# flatsat-breakout-main.net
KiCad netlist of a schematic drawn in EAGLE
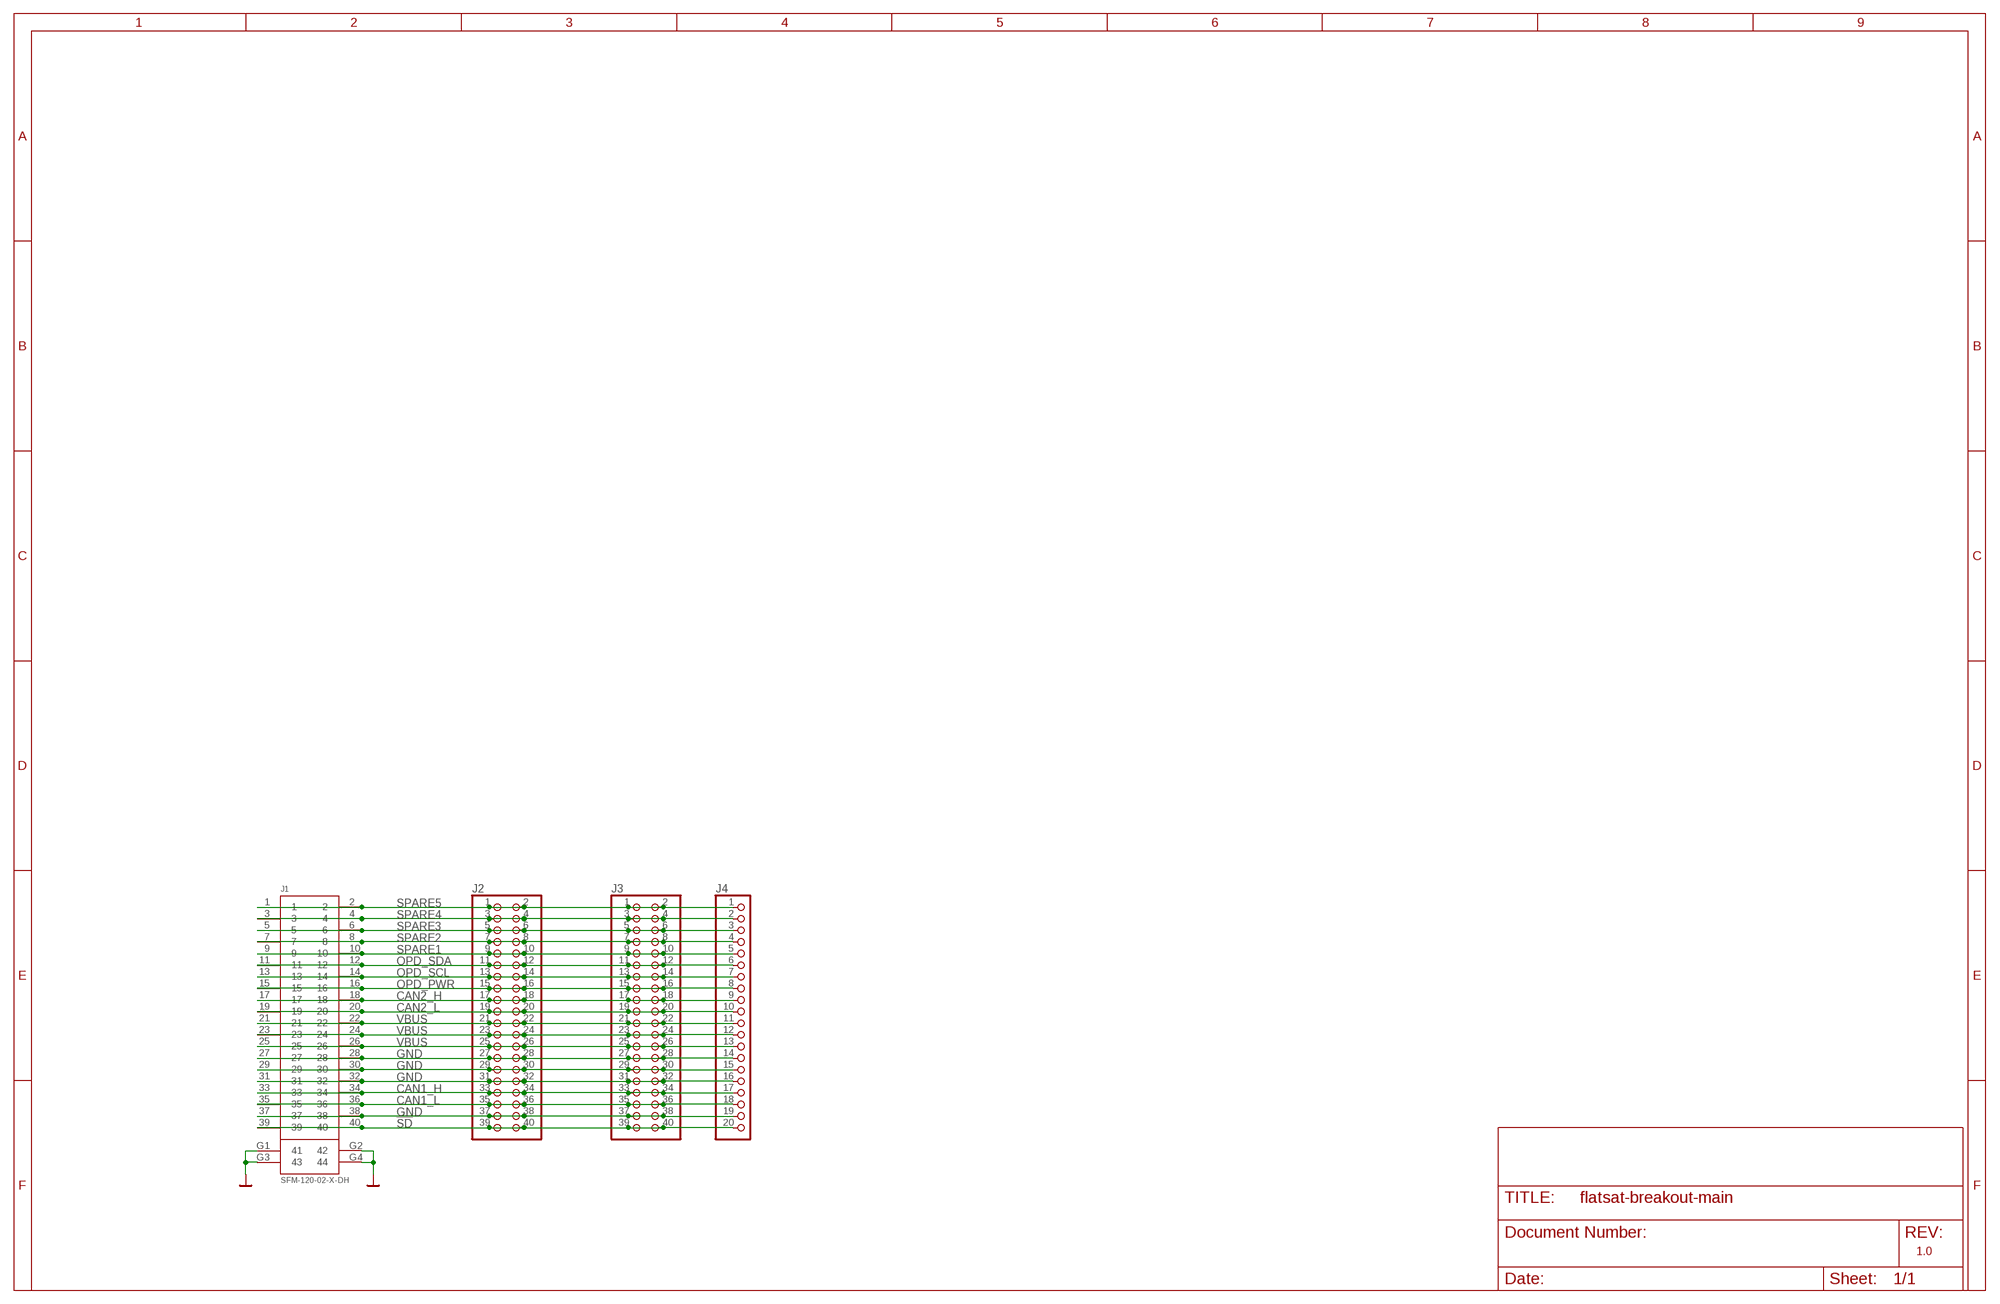
[diagram p0: schematic, sheet 1]

(export (version "E")
  (design (tool "Eeschema 10.0.6"))
  (components
    (comp (ref "J1")
      (value "SFM-120-02-X-DH")
      (footprint "eagle-import:SFM-120-02-X-DH")
      (libsource (lib "eagle-import") (part "SFM-120-02-X-DH"))
    )
    (comp (ref "J2")
      (value "PINHD-2X20")
      (footprint "eagle-import:2X20")
      (libsource (lib "eagle-import") (part "PINHD-2X20"))
    )
    (comp (ref "J3")
      (value "PINHD-2X20")
      (footprint "eagle-import:2X20")
      (libsource (lib "eagle-import") (part "PINHD-2X20"))
    )
    (comp (ref "J4")
      (value "PINHD-1X20")
      (footprint "eagle-import:1X20")
      (libsource (lib "eagle-import") (part "PINHD-1X20"))
    )
  )
  (nets
    (net (code "1") (name "/CAN1_H") (class "Default")
      (node (ref "J1") (pin "33") (pinfunction "33_33") (pintype "bidirectional"))
      (node (ref "J1") (pin "34") (pinfunction "34_34") (pintype "bidirectional"))
      (node (ref "J2") (pin "33") (pinfunction "33_33") (pintype "passive"))
      (node (ref "J2") (pin "34") (pinfunction "34_34") (pintype "passive"))
      (node (ref "J3") (pin "33") (pinfunction "33_33") (pintype "passive"))
      (node (ref "J3") (pin "34") (pinfunction "34_34") (pintype "passive"))
      (node (ref "J4") (pin "17") (pinfunction "17_17") (pintype "passive"))
    )
    (net (code "2") (name "/CAN1_L") (class "Default")
      (node (ref "J1") (pin "35") (pinfunction "35_35") (pintype "bidirectional"))
      (node (ref "J1") (pin "36") (pinfunction "36_36") (pintype "bidirectional"))
      (node (ref "J2") (pin "35") (pinfunction "35_35") (pintype "passive"))
      (node (ref "J2") (pin "36") (pinfunction "36_36") (pintype "passive"))
      (node (ref "J3") (pin "35") (pinfunction "35_35") (pintype "passive"))
      (node (ref "J3") (pin "36") (pinfunction "36_36") (pintype "passive"))
      (node (ref "J4") (pin "18") (pinfunction "18_18") (pintype "passive"))
    )
    (net (code "3") (name "/CAN2_H") (class "Default")
      (node (ref "J1") (pin "17") (pinfunction "17_17") (pintype "bidirectional"))
      (node (ref "J1") (pin "18") (pinfunction "18_18") (pintype "bidirectional"))
      (node (ref "J2") (pin "17") (pinfunction "17_17") (pintype "passive"))
      (node (ref "J2") (pin "18") (pinfunction "18_18") (pintype "passive"))
      (node (ref "J3") (pin "17") (pinfunction "17_17") (pintype "passive"))
      (node (ref "J3") (pin "18") (pinfunction "18_18") (pintype "passive"))
      (node (ref "J4") (pin "9") (pinfunction "9_9") (pintype "passive"))
    )
    (net (code "4") (name "/CAN2_L") (class "Default")
      (node (ref "J1") (pin "19") (pinfunction "19_19") (pintype "bidirectional"))
      (node (ref "J1") (pin "20") (pinfunction "20_20") (pintype "bidirectional"))
      (node (ref "J2") (pin "19") (pinfunction "19_19") (pintype "passive"))
      (node (ref "J2") (pin "20") (pinfunction "20_20") (pintype "passive"))
      (node (ref "J3") (pin "19") (pinfunction "19_19") (pintype "passive"))
      (node (ref "J3") (pin "20") (pinfunction "20_20") (pintype "passive"))
      (node (ref "J4") (pin "10") (pinfunction "10_10") (pintype "passive"))
    )
    (net (code "5") (name "/OPD_PWR") (class "Default")
      (node (ref "J1") (pin "15") (pinfunction "15_15") (pintype "bidirectional"))
      (node (ref "J1") (pin "16") (pinfunction "16_16") (pintype "bidirectional"))
      (node (ref "J2") (pin "15") (pinfunction "15_15") (pintype "passive"))
      (node (ref "J2") (pin "16") (pinfunction "16_16") (pintype "passive"))
      (node (ref "J3") (pin "15") (pinfunction "15_15") (pintype "passive"))
      (node (ref "J3") (pin "16") (pinfunction "16_16") (pintype "passive"))
      (node (ref "J4") (pin "8") (pinfunction "8_8") (pintype "passive"))
    )
    (net (code "6") (name "/OPD_SCL") (class "Default")
      (node (ref "J1") (pin "13") (pinfunction "13_13") (pintype "bidirectional"))
      (node (ref "J1") (pin "14") (pinfunction "14_14") (pintype "bidirectional"))
      (node (ref "J2") (pin "13") (pinfunction "13_13") (pintype "passive"))
      (node (ref "J2") (pin "14") (pinfunction "14_14") (pintype "passive"))
      (node (ref "J3") (pin "13") (pinfunction "13_13") (pintype "passive"))
      (node (ref "J3") (pin "14") (pinfunction "14_14") (pintype "passive"))
      (node (ref "J4") (pin "7") (pinfunction "7_7") (pintype "passive"))
    )
    (net (code "7") (name "/OPD_SDA") (class "Default")
      (node (ref "J1") (pin "11") (pinfunction "11_11") (pintype "bidirectional"))
      (node (ref "J1") (pin "12") (pinfunction "12_12") (pintype "bidirectional"))
      (node (ref "J2") (pin "11") (pinfunction "11_11") (pintype "passive"))
      (node (ref "J2") (pin "12") (pinfunction "12_12") (pintype "passive"))
      (node (ref "J3") (pin "11") (pinfunction "11_11") (pintype "passive"))
      (node (ref "J3") (pin "12") (pinfunction "12_12") (pintype "passive"))
      (node (ref "J4") (pin "6") (pinfunction "6_6") (pintype "passive"))
    )
    (net (code "8") (name "/SPARE1") (class "Default")
      (node (ref "J1") (pin "10") (pinfunction "10_10") (pintype "bidirectional"))
      (node (ref "J1") (pin "9") (pinfunction "9_9") (pintype "bidirectional"))
      (node (ref "J2") (pin "10") (pinfunction "10_10") (pintype "passive"))
      (node (ref "J2") (pin "9") (pinfunction "9_9") (pintype "passive"))
      (node (ref "J3") (pin "10") (pinfunction "10_10") (pintype "passive"))
      (node (ref "J3") (pin "9") (pinfunction "9_9") (pintype "passive"))
      (node (ref "J4") (pin "5") (pinfunction "5_5") (pintype "passive"))
    )
    (net (code "9") (name "/SPARE2") (class "Default")
      (node (ref "J1") (pin "7") (pinfunction "7_7") (pintype "bidirectional"))
      (node (ref "J1") (pin "8") (pinfunction "8_8") (pintype "bidirectional"))
      (node (ref "J2") (pin "7") (pinfunction "7_7") (pintype "passive"))
      (node (ref "J2") (pin "8") (pinfunction "8_8") (pintype "passive"))
      (node (ref "J3") (pin "7") (pinfunction "7_7") (pintype "passive"))
      (node (ref "J3") (pin "8") (pinfunction "8_8") (pintype "passive"))
      (node (ref "J4") (pin "4") (pinfunction "4_4") (pintype "passive"))
    )
    (net (code "10") (name "/SPARE3") (class "Default")
      (node (ref "J1") (pin "5") (pinfunction "5_5") (pintype "bidirectional"))
      (node (ref "J1") (pin "6") (pinfunction "6_6") (pintype "bidirectional"))
      (node (ref "J2") (pin "5") (pinfunction "5_5") (pintype "passive"))
      (node (ref "J2") (pin "6") (pinfunction "6_6") (pintype "passive"))
      (node (ref "J3") (pin "5") (pinfunction "5_5") (pintype "passive"))
      (node (ref "J3") (pin "6") (pinfunction "6_6") (pintype "passive"))
      (node (ref "J4") (pin "3") (pinfunction "3_3") (pintype "passive"))
    )
    (net (code "11") (name "/SPARE4") (class "Default")
      (node (ref "J1") (pin "3") (pinfunction "3_3") (pintype "bidirectional"))
      (node (ref "J1") (pin "4") (pinfunction "4_4") (pintype "bidirectional"))
      (node (ref "J2") (pin "3") (pinfunction "3_3") (pintype "passive"))
      (node (ref "J2") (pin "4") (pinfunction "4_4") (pintype "passive"))
      (node (ref "J3") (pin "3") (pinfunction "3_3") (pintype "passive"))
      (node (ref "J3") (pin "4") (pinfunction "4_4") (pintype "passive"))
      (node (ref "J4") (pin "2") (pinfunction "2_2") (pintype "passive"))
    )
    (net (code "12") (name "/SPARE5") (class "Default")
      (node (ref "J1") (pin "1") (pinfunction "1_1") (pintype "bidirectional"))
      (node (ref "J1") (pin "2") (pinfunction "2_2") (pintype "bidirectional"))
      (node (ref "J2") (pin "1") (pinfunction "1_1") (pintype "passive"))
      (node (ref "J2") (pin "2") (pinfunction "2_2") (pintype "passive"))
      (node (ref "J3") (pin "1") (pinfunction "1_1") (pintype "passive"))
      (node (ref "J3") (pin "2") (pinfunction "2_2") (pintype "passive"))
      (node (ref "J4") (pin "1") (pinfunction "1_1") (pintype "passive"))
    )
    (net (code "13") (name "/VBUS") (class "Default")
      (node (ref "J1") (pin "21") (pinfunction "21_21") (pintype "bidirectional"))
      (node (ref "J1") (pin "22") (pinfunction "22_22") (pintype "bidirectional"))
      (node (ref "J1") (pin "23") (pinfunction "23_23") (pintype "bidirectional"))
      (node (ref "J1") (pin "24") (pinfunction "24_24") (pintype "bidirectional"))
      (node (ref "J1") (pin "25") (pinfunction "25_25") (pintype "bidirectional"))
      (node (ref "J1") (pin "26") (pinfunction "26_26") (pintype "bidirectional"))
      (node (ref "J2") (pin "21") (pinfunction "21_21") (pintype "passive"))
      (node (ref "J2") (pin "22") (pinfunction "22_22") (pintype "passive"))
      (node (ref "J2") (pin "23") (pinfunction "23_23") (pintype "passive"))
      (node (ref "J2") (pin "24") (pinfunction "24_24") (pintype "passive"))
      (node (ref "J2") (pin "25") (pinfunction "25_25") (pintype "passive"))
      (node (ref "J2") (pin "26") (pinfunction "26_26") (pintype "passive"))
      (node (ref "J3") (pin "21") (pinfunction "21_21") (pintype "passive"))
      (node (ref "J3") (pin "22") (pinfunction "22_22") (pintype "passive"))
      (node (ref "J3") (pin "23") (pinfunction "23_23") (pintype "passive"))
      (node (ref "J3") (pin "24") (pinfunction "24_24") (pintype "passive"))
      (node (ref "J3") (pin "25") (pinfunction "25_25") (pintype "passive"))
      (node (ref "J3") (pin "26") (pinfunction "26_26") (pintype "passive"))
      (node (ref "J4") (pin "11") (pinfunction "11_11") (pintype "passive"))
      (node (ref "J4") (pin "12") (pinfunction "12_12") (pintype "passive"))
      (node (ref "J4") (pin "13") (pinfunction "13_13") (pintype "passive"))
    )
    (net (code "14") (name "/~{SD}") (class "Default")
      (node (ref "J1") (pin "39") (pinfunction "39_39") (pintype "bidirectional"))
      (node (ref "J1") (pin "40") (pinfunction "40_40") (pintype "bidirectional"))
      (node (ref "J2") (pin "39") (pinfunction "39_39") (pintype "passive"))
      (node (ref "J2") (pin "40") (pinfunction "40_40") (pintype "passive"))
      (node (ref "J3") (pin "39") (pinfunction "39_39") (pintype "passive"))
      (node (ref "J3") (pin "40") (pinfunction "40_40") (pintype "passive"))
      (node (ref "J4") (pin "20") (pinfunction "20_20") (pintype "passive"))
    )
    (net (code "15") (name "GND") (class "Default")
      (node (ref "J1") (pin "27") (pinfunction "27_27") (pintype "bidirectional"))
      (node (ref "J1") (pin "28") (pinfunction "28_28") (pintype "bidirectional"))
      (node (ref "J1") (pin "29") (pinfunction "29_29") (pintype "bidirectional"))
      (node (ref "J1") (pin "30") (pinfunction "30_30") (pintype "bidirectional"))
      (node (ref "J1") (pin "31") (pinfunction "31_31") (pintype "bidirectional"))
      (node (ref "J1") (pin "32") (pinfunction "32_32") (pintype "bidirectional"))
      (node (ref "J1") (pin "37") (pinfunction "37_37") (pintype "bidirectional"))
      (node (ref "J1") (pin "38") (pinfunction "38_38") (pintype "bidirectional"))
      (node (ref "J1") (pin "G1") (pinfunction "41_G1") (pintype "bidirectional"))
      (node (ref "J1") (pin "G2") (pinfunction "42_G2") (pintype "bidirectional"))
      (node (ref "J1") (pin "G3") (pinfunction "43_G3") (pintype "bidirectional"))
      (node (ref "J1") (pin "G4") (pinfunction "44_G4") (pintype "bidirectional"))
      (node (ref "J2") (pin "27") (pinfunction "27_27") (pintype "passive"))
      (node (ref "J2") (pin "28") (pinfunction "28_28") (pintype "passive"))
      (node (ref "J2") (pin "29") (pinfunction "29_29") (pintype "passive"))
      (node (ref "J2") (pin "30") (pinfunction "30_30") (pintype "passive"))
      (node (ref "J2") (pin "31") (pinfunction "31_31") (pintype "passive"))
      (node (ref "J2") (pin "32") (pinfunction "32_32") (pintype "passive"))
      (node (ref "J2") (pin "37") (pinfunction "37_37") (pintype "passive"))
      (node (ref "J2") (pin "38") (pinfunction "38_38") (pintype "passive"))
      (node (ref "J3") (pin "27") (pinfunction "27_27") (pintype "passive"))
      (node (ref "J3") (pin "28") (pinfunction "28_28") (pintype "passive"))
      (node (ref "J3") (pin "29") (pinfunction "29_29") (pintype "passive"))
      (node (ref "J3") (pin "30") (pinfunction "30_30") (pintype "passive"))
      (node (ref "J3") (pin "31") (pinfunction "31_31") (pintype "passive"))
      (node (ref "J3") (pin "32") (pinfunction "32_32") (pintype "passive"))
      (node (ref "J3") (pin "37") (pinfunction "37_37") (pintype "passive"))
      (node (ref "J3") (pin "38") (pinfunction "38_38") (pintype "passive"))
      (node (ref "J4") (pin "14") (pinfunction "14_14") (pintype "passive"))
      (node (ref "J4") (pin "15") (pinfunction "15_15") (pintype "passive"))
      (node (ref "J4") (pin "16") (pinfunction "16_16") (pintype "passive"))
      (node (ref "J4") (pin "19") (pinfunction "19_19") (pintype "passive"))
    )
  )
)
